# BreaV5.net
KiCad netlist of a schematic drawn in EAGLE
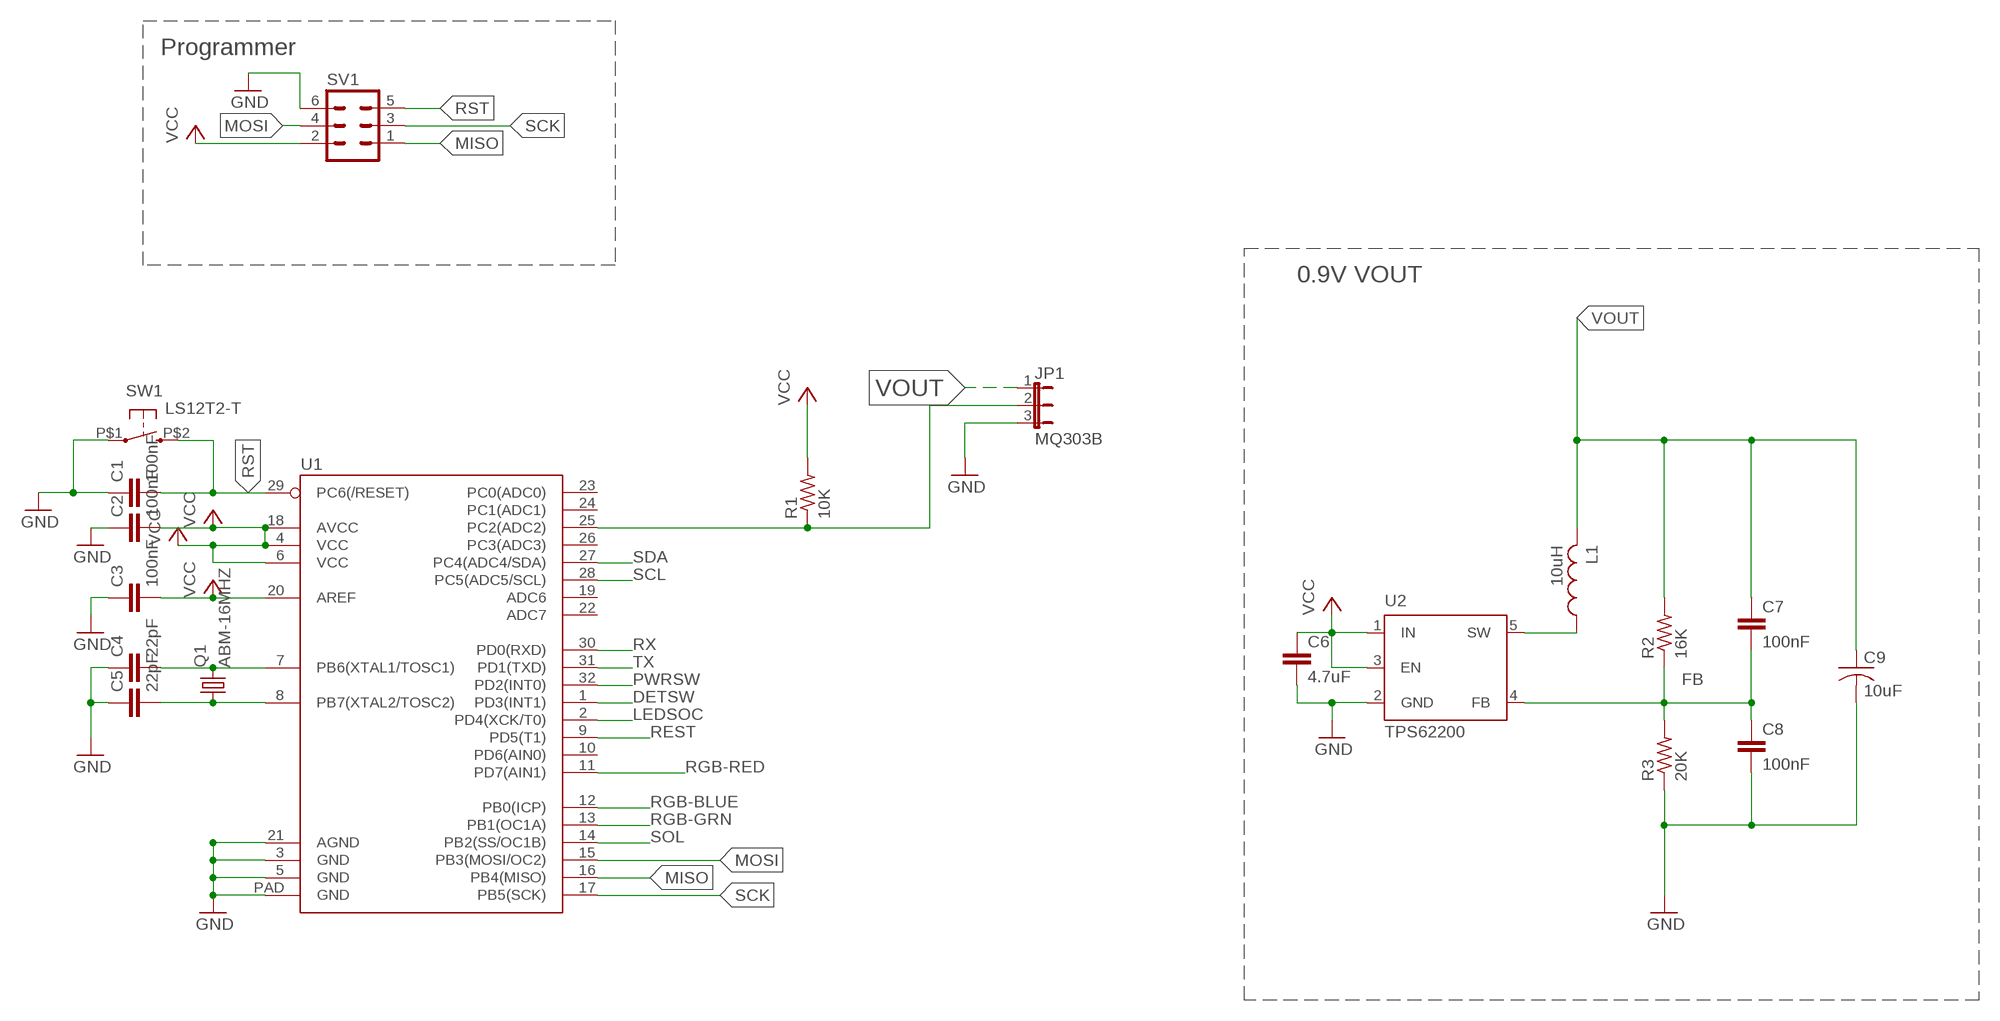
[diagram p0: schematic, sheet 1]
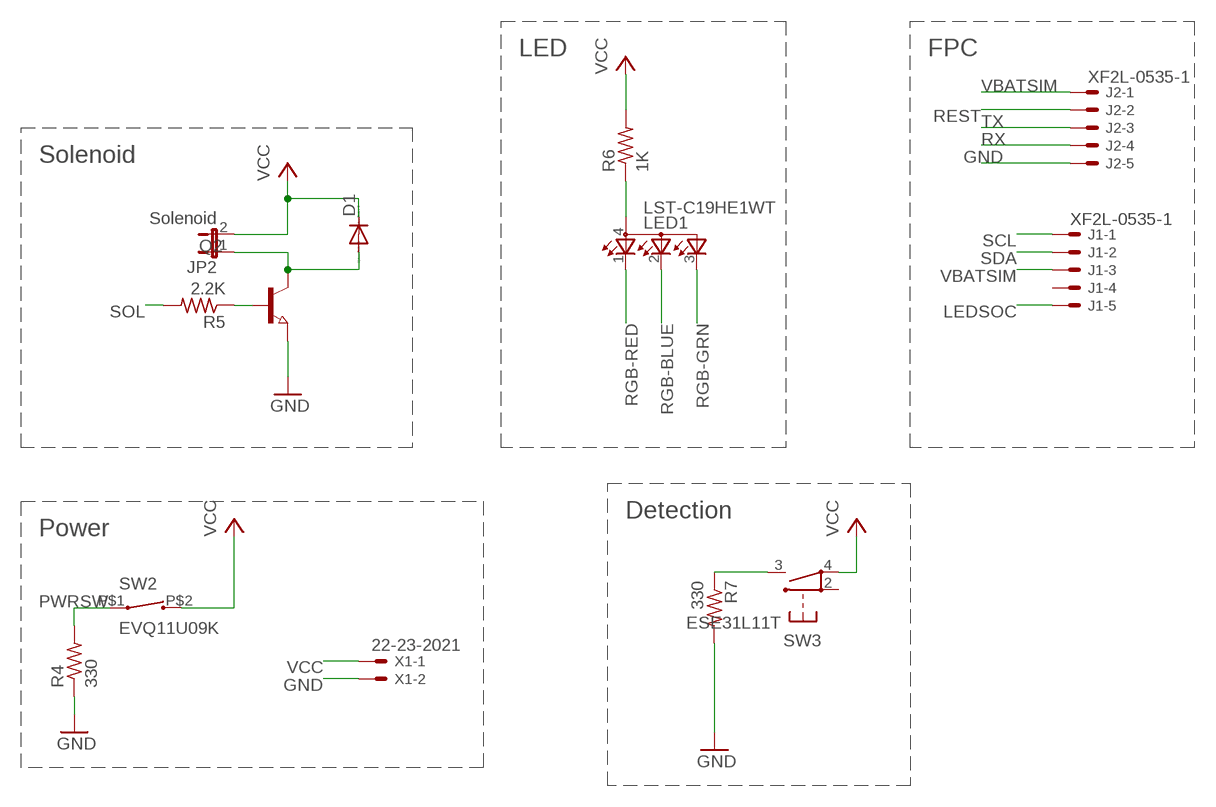
[diagram p1: schematic, sheet 2]

(export (version "E")
  (design (tool "Eeschema 10.0.6"))
  (components
    (comp (ref "C1")
      (value "100nF")
      (footprint "eagle-import:C0603")
      (libsource (lib "eagle-import") (part "C-EUC0603"))
    )
    (comp (ref "C2")
      (value "100nF")
      (footprint "eagle-import:C0603")
      (libsource (lib "eagle-import") (part "C-EUC0603"))
    )
    (comp (ref "C3")
      (value "100nF")
      (footprint "eagle-import:C0603")
      (libsource (lib "eagle-import") (part "C-EUC0603"))
    )
    (comp (ref "C4")
      (value "22pF")
      (footprint "eagle-import:C0603")
      (libsource (lib "eagle-import") (part "C-EUC0603"))
    )
    (comp (ref "C5")
      (value "22pF")
      (footprint "eagle-import:C0603")
      (libsource (lib "eagle-import") (part "C-EUC0603"))
    )
    (comp (ref "C6")
      (value "4.7uF")
      (footprint "eagle-import:C0402")
      (libsource (lib "eagle-import") (part "C-EUC0402"))
    )
    (comp (ref "C7")
      (value "100nF")
      (footprint "eagle-import:C0402")
      (libsource (lib "eagle-import") (part "C-EUC0402"))
    )
    (comp (ref "C8")
      (value "100nF")
      (footprint "eagle-import:C0402")
      (libsource (lib "eagle-import") (part "C-EUC0402"))
    )
    (comp (ref "C9")
      (value "10uF")
      (footprint "eagle-import:C0805K")
      (libsource (lib "eagle-import") (part "C-USC0805K"))
    )
    (comp (ref "JP1")
      (value "MQ303B")
      (footprint "eagle-import:JP2")
      (libsource (lib "eagle-import") (part "JP2E"))
    )
    (comp (ref "L1")
      (value "10uH")
      (footprint "eagle-import:L2825P")
      (libsource (lib "eagle-import") (part "L-USL2825P"))
    )
    (comp (ref "Q1")
      (value "ABM-16MHZ")
      (footprint "eagle-import:ABM-16MHZ")
      (libsource (lib "eagle-import") (part "ABM-16MHZ"))
    )
    (comp (ref "R1")
      (value "10K")
      (footprint "eagle-import:R0402")
      (libsource (lib "eagle-import") (part "R-US_R0402"))
    )
    (comp (ref "R2")
      (value "16K")
      (footprint "eagle-import:R0402")
      (libsource (lib "eagle-import") (part "R-US_R0402"))
    )
    (comp (ref "R3")
      (value "20K")
      (footprint "eagle-import:R0402")
      (libsource (lib "eagle-import") (part "R-US_R0402"))
    )
    (comp (ref "SV1")
      (value "MA03-2")
      (footprint "eagle-import:MA03-2")
      (libsource (lib "eagle-import") (part "MA03-2"))
    )
    (comp (ref "SW1")
      (value "LS12T2-T")
      (footprint "eagle-import:LS12T2-T")
      (libsource (lib "eagle-import") (part "LS12T2-T"))
    )
    (comp (ref "U1")
      (value "ATMEGA328P_MLFMLF32")
      (footprint "eagle-import:MLF32-PAD")
      (libsource (lib "eagle-import") (part "ATMEGA328P_MLFMLF32"))
    )
    (comp (ref "U2")
      (value "TPS62200")
      (footprint "eagle-import:TPS62200")
      (libsource (lib "eagle-import") (part "TPS62200"))
    )
    (comp (ref "D1")
      (value "DIODE-SOD123")
      (footprint "eagle-import:SOD123")
      (libsource (lib "eagle-import") (part "DIODE-SOD123"))
    )
    (comp (ref "J1")
      (value "XF2L-0535-1")
      (footprint "eagle-import:XF2L-0535-1")
      (libsource (lib "eagle-import") (part "XF2-05?35-1L"))
    )
    (comp (ref "J2")
      (value "XF2L-0535-1")
      (footprint "eagle-import:XF2L-0535-1")
      (libsource (lib "eagle-import") (part "XF2-05?35-1L"))
    )
    (comp (ref "JP2")
      (value "Solenoid")
      (footprint "eagle-import:JP1")
      (libsource (lib "eagle-import") (part "JP1E"))
    )
    (comp (ref "LED1")
      (value "LST-C19HE1WT")
      (footprint "eagle-import:LST-C19HE1WT")
      (libsource (lib "eagle-import") (part "LST-C19HE1WT"))
    )
    (comp (ref "Q2")
      (value "NPN-TRANSISTOR_SOT23")
      (footprint "eagle-import:SOT23")
      (libsource (lib "eagle-import") (part "NPN-TRANSISTOR_SOT23"))
    )
    (comp (ref "R4")
      (value "330")
      (footprint "eagle-import:R0402")
      (libsource (lib "eagle-import") (part "R-US_R0402"))
    )
    (comp (ref "R5")
      (value "2.2K")
      (footprint "eagle-import:R0402")
      (libsource (lib "eagle-import") (part "R-US_R0402"))
    )
    (comp (ref "R6")
      (value "1K")
      (footprint "eagle-import:R0402")
      (libsource (lib "eagle-import") (part "R-US_R0402"))
    )
    (comp (ref "R7")
      (value "330")
      (footprint "eagle-import:R0402")
      (libsource (lib "eagle-import") (part "R-US_R0402"))
    )
    (comp (ref "SW2")
      (value "EVQ11U09K")
      (footprint "eagle-import:EVQ11U-09K")
      (libsource (lib "eagle-import") (part "EVQ11U09K"))
    )
    (comp (ref "SW3")
      (value "ESE31L11T")
      (footprint "eagle-import:SWITCH")
      (libsource (lib "eagle-import") (part "ESE31L11T"))
    )
    (comp (ref "X1")
      (value "22-23-2021")
      (footprint "eagle-import:22-23-2021")
      (fields (field (name "MF") "MOLEX"))
      (libsource (lib "eagle-import") (part "22-23-2021"))
    )
  )
  (nets
    (net (code "1") (name "DETSW") (class "Default")
      (node (ref "R7") (pin "1") (pinfunction "1_1") (pintype "passive"))
      (node (ref "SW3") (pin "3") (pinfunction "1_3") (pintype "passive"))
      (node (ref "U1") (pin "1") (pinfunction "PD3(INT1)_1") (pintype "bidirectional"))
    )
    (net (code "2") (name "FB") (class "Default")
      (node (ref "C7") (pin "2") (pinfunction "2_2") (pintype "passive"))
      (node (ref "C8") (pin "1") (pinfunction "1_1") (pintype "passive"))
      (node (ref "R2") (pin "1") (pinfunction "1_1") (pintype "passive"))
      (node (ref "R3") (pin "2") (pinfunction "2_2") (pintype "passive"))
      (node (ref "U2") (pin "4") (pinfunction "FB_4") (pintype "passive"))
    )
    (net (code "3") (name "GND") (class "Default")
      (node (ref "C1") (pin "1") (pinfunction "1_1") (pintype "passive"))
      (node (ref "C2") (pin "1") (pinfunction "1_1") (pintype "passive"))
      (node (ref "C3") (pin "1") (pinfunction "1_1") (pintype "passive"))
      (node (ref "C4") (pin "1") (pinfunction "1_1") (pintype "passive"))
      (node (ref "C5") (pin "1") (pinfunction "1_1") (pintype "passive"))
      (node (ref "C6") (pin "2") (pinfunction "2_2") (pintype "passive"))
      (node (ref "C8") (pin "2") (pinfunction "2_2") (pintype "passive"))
      (node (ref "C9") (pin "2") (pinfunction "2_2") (pintype "passive"))
      (node (ref "J2") (pin "5") (pinfunction "MS_5") (pintype "passive"))
      (node (ref "JP1") (pin "3") (pinfunction "3_3") (pintype "passive"))
      (node (ref "Q2") (pin "2") (pinfunction "E_2") (pintype "passive"))
      (node (ref "R3") (pin "1") (pinfunction "1_1") (pintype "passive"))
      (node (ref "R4") (pin "1") (pinfunction "1_1") (pintype "passive"))
      (node (ref "R7") (pin "2") (pinfunction "2_2") (pintype "passive"))
      (node (ref "SV1") (pin "6") (pinfunction "MISO_6") (pintype "passive"))
      (node (ref "SW1") (pin "P$1") (pinfunction "S1_P$1") (pintype "passive"))
      (node (ref "U1") (pin "21") (pinfunction "AGND_21") (pintype "bidirectional"))
      (node (ref "U1") (pin "3") (pinfunction "GND_3") (pintype "bidirectional"))
      (node (ref "U1") (pin "5") (pinfunction "GND_5") (pintype "bidirectional"))
      (node (ref "U1") (pin "PAD") (pinfunction "GND_PAD") (pintype "bidirectional"))
      (node (ref "U2") (pin "2") (pinfunction "GND_2") (pintype "power_in"))
      (node (ref "X1") (pin "2") (pinfunction "S_2") (pintype "passive"))
    )
    (net (code "4") (name "LEDSOC") (class "Default")
      (node (ref "J1") (pin "5") (pinfunction "MS_5") (pintype "passive"))
      (node (ref "U1") (pin "2") (pinfunction "PD4(XCK/T0)_2") (pintype "bidirectional"))
    )
    (net (code "5") (name "MISO") (class "Default")
      (node (ref "SV1") (pin "1") (pinfunction "1_1") (pintype "passive"))
      (node (ref "U1") (pin "16") (pinfunction "PB4(MISO)_16") (pintype "bidirectional"))
    )
    (net (code "6") (name "MOSI") (class "Default")
      (node (ref "SV1") (pin "4") (pinfunction "4_4") (pintype "passive"))
      (node (ref "U1") (pin "15") (pinfunction "PB3(MOSI/OC2)_15") (pintype "bidirectional"))
    )
    (net (code "7") (name "Net-(LED1-A)") (class "Default")
      (node (ref "LED1") (pin "4") (pinfunction "A_4") (pintype "passive"))
      (node (ref "R6") (pin "1") (pinfunction "1_1") (pintype "passive"))
    )
    (net (code "8") (name "Net-(Q1-1)") (class "Default")
      (node (ref "C5") (pin "2") (pinfunction "2_2") (pintype "passive"))
      (node (ref "Q1") (pin "P$1") (pinfunction "1_P$1") (pintype "passive"))
      (node (ref "U1") (pin "8") (pinfunction "PB7(XTAL2/TOSC2)_8") (pintype "bidirectional"))
    )
    (net (code "9") (name "Net-(Q1-2)") (class "Default")
      (node (ref "C4") (pin "2") (pinfunction "2_2") (pintype "passive"))
      (node (ref "Q1") (pin "P$2") (pinfunction "2_P$2") (pintype "passive"))
      (node (ref "U1") (pin "7") (pinfunction "PB6(XTAL1/TOSC1)_7") (pintype "bidirectional"))
    )
    (net (code "10") (name "Net-(Q2-B)") (class "Default")
      (node (ref "Q2") (pin "1") (pinfunction "B_1") (pintype "passive"))
      (node (ref "R5") (pin "1") (pinfunction "1_1") (pintype "passive"))
    )
    (net (code "11") (name "Net-(Q2-C)") (class "Default")
      (node (ref "D1") (pin "A") (pinfunction "A_A") (pintype "passive"))
      (node (ref "JP2") (pin "1") (pinfunction "1_1") (pintype "passive"))
      (node (ref "Q2") (pin "3") (pinfunction "C_3") (pintype "passive"))
    )
    (net (code "12") (name "Net-(U1-PC2(ADC2))") (class "Default")
      (node (ref "JP1") (pin "2") (pinfunction "2_2") (pintype "passive"))
      (node (ref "R1") (pin "1") (pinfunction "1_1") (pintype "passive"))
      (node (ref "U1") (pin "25") (pinfunction "PC2(ADC2)_25") (pintype "bidirectional"))
    )
    (net (code "13") (name "Net-(U2-SW)") (class "Default")
      (node (ref "L1") (pin "1") (pinfunction "1_1") (pintype "passive"))
      (node (ref "U2") (pin "5") (pinfunction "SW_5") (pintype "passive"))
    )
    (net (code "14") (name "PWRSW") (class "Default")
      (node (ref "R4") (pin "2") (pinfunction "2_2") (pintype "passive"))
      (node (ref "SW2") (pin "P$1") (pinfunction "1_P$1") (pintype "passive"))
      (node (ref "U1") (pin "32") (pinfunction "PD2(INT0)_32") (pintype "bidirectional"))
    )
    (net (code "15") (name "REST") (class "Default")
      (node (ref "J2") (pin "2") (pinfunction "MS_2") (pintype "passive"))
      (node (ref "U1") (pin "9") (pinfunction "PD5(T1)_9") (pintype "bidirectional"))
    )
    (net (code "16") (name "RGB-BLUE") (class "Default")
      (node (ref "LED1") (pin "2") (pinfunction "CGREEN_2") (pintype "passive"))
      (node (ref "U1") (pin "12") (pinfunction "PB0(ICP)_12") (pintype "bidirectional"))
    )
    (net (code "17") (name "RGB-GRN") (class "Default")
      (node (ref "LED1") (pin "3") (pinfunction "CBLUE_3") (pintype "passive"))
      (node (ref "U1") (pin "13") (pinfunction "PB1(OC1A)_13") (pintype "bidirectional"))
    )
    (net (code "18") (name "RGB-RED") (class "Default")
      (node (ref "LED1") (pin "1") (pinfunction "CRED_1") (pintype "passive"))
      (node (ref "U1") (pin "11") (pinfunction "PD7(AIN1)_11") (pintype "bidirectional"))
    )
    (net (code "19") (name "RST") (class "Default")
      (node (ref "C1") (pin "2") (pinfunction "2_2") (pintype "passive"))
      (node (ref "SV1") (pin "5") (pinfunction "VTG_5") (pintype "passive"))
      (node (ref "SW1") (pin "P$2") (pinfunction "S2_P$2") (pintype "passive"))
      (node (ref "U1") (pin "29") (pinfunction "PC6(/RESET)_29") (pintype "bidirectional"))
    )
    (net (code "20") (name "RX") (class "Default")
      (node (ref "J2") (pin "4") (pinfunction "MS_4") (pintype "passive"))
      (node (ref "U1") (pin "30") (pinfunction "PD0(RXD)_30") (pintype "bidirectional"))
    )
    (net (code "21") (name "SCK") (class "Default")
      (node (ref "SV1") (pin "3") (pinfunction "3_3") (pintype "passive"))
      (node (ref "U1") (pin "17") (pinfunction "PB5(SCK)_17") (pintype "bidirectional"))
    )
    (net (code "22") (name "SCL") (class "Default")
      (node (ref "J1") (pin "1") (pinfunction "MSV_1") (pintype "passive"))
      (node (ref "U1") (pin "28") (pinfunction "PC5(ADC5/SCL)_28") (pintype "bidirectional"))
    )
    (net (code "23") (name "SDA") (class "Default")
      (node (ref "J1") (pin "2") (pinfunction "MS_2") (pintype "passive"))
      (node (ref "U1") (pin "27") (pinfunction "PC4(ADC4/SDA)_27") (pintype "bidirectional"))
    )
    (net (code "24") (name "SOL") (class "Default")
      (node (ref "R5") (pin "2") (pinfunction "2_2") (pintype "passive"))
      (node (ref "U1") (pin "14") (pinfunction "PB2(SS/OC1B)_14") (pintype "bidirectional"))
    )
    (net (code "25") (name "TX") (class "Default")
      (node (ref "J2") (pin "3") (pinfunction "MS_3") (pintype "passive"))
      (node (ref "U1") (pin "31") (pinfunction "PD1(TXD)_31") (pintype "bidirectional"))
    )
    (net (code "26") (name "VBATSIM") (class "Default")
      (node (ref "J1") (pin "3") (pinfunction "MS_3") (pintype "passive"))
      (node (ref "J2") (pin "1") (pinfunction "MSV_1") (pintype "passive"))
    )
    (net (code "27") (name "VCC") (class "Default")
      (node (ref "C2") (pin "2") (pinfunction "2_2") (pintype "passive"))
      (node (ref "C3") (pin "2") (pinfunction "2_2") (pintype "passive"))
      (node (ref "C6") (pin "1") (pinfunction "1_1") (pintype "passive"))
      (node (ref "D1") (pin "C") (pinfunction "C_C") (pintype "passive"))
      (node (ref "JP2") (pin "2") (pinfunction "2_2") (pintype "passive"))
      (node (ref "R1") (pin "2") (pinfunction "2_2") (pintype "passive"))
      (node (ref "R6") (pin "2") (pinfunction "2_2") (pintype "passive"))
      (node (ref "SV1") (pin "2") (pinfunction "2_2") (pintype "passive"))
      (node (ref "SW2") (pin "P$2") (pinfunction "2_P$2") (pintype "passive"))
      (node (ref "SW3") (pin "4") (pinfunction "C3_4") (pintype "passive"))
      (node (ref "U1") (pin "18") (pinfunction "AVCC_18") (pintype "bidirectional"))
      (node (ref "U1") (pin "20") (pinfunction "AREF_20") (pintype "bidirectional"))
      (node (ref "U1") (pin "4") (pinfunction "VCC_4") (pintype "bidirectional"))
      (node (ref "U1") (pin "6") (pinfunction "VCC_6") (pintype "bidirectional"))
      (node (ref "U2") (pin "1") (pinfunction "IN_1") (pintype "input"))
      (node (ref "U2") (pin "3") (pinfunction "EN_3") (pintype "input"))
      (node (ref "X1") (pin "1") (pinfunction "S_1") (pintype "passive"))
    )
    (net (code "28") (name "VOUT") (class "Default")
      (node (ref "C7") (pin "1") (pinfunction "1_1") (pintype "passive"))
      (node (ref "C9") (pin "1") (pinfunction "1_1") (pintype "passive"))
      (node (ref "JP1") (pin "1") (pinfunction "1_1") (pintype "passive"))
      (node (ref "L1") (pin "2") (pinfunction "2_2") (pintype "passive"))
      (node (ref "R2") (pin "2") (pinfunction "2_2") (pintype "passive"))
    )
    (net (code "29") (name "unconnected-(J1D-MS-Pad4)") (class "Default")
      (node (ref "J1") (pin "4") (pinfunction "MS_4") (pintype "passive"))
    )
    (net (code "30") (name "unconnected-(SW3-C2-Pad2)") (class "Default")
      (node (ref "SW3") (pin "2") (pinfunction "C2_2") (pintype "passive"))
    )
    (net (code "31") (name "unconnected-(U1-ADC6-Pad19)") (class "Default")
      (node (ref "U1") (pin "19") (pinfunction "ADC6_19") (pintype "bidirectional"))
    )
    (net (code "32") (name "unconnected-(U1-ADC7-Pad22)") (class "Default")
      (node (ref "U1") (pin "22") (pinfunction "ADC7_22") (pintype "bidirectional"))
    )
    (net (code "33") (name "unconnected-(U1-PC0(ADC0)-Pad23)") (class "Default")
      (node (ref "U1") (pin "23") (pinfunction "PC0(ADC0)_23") (pintype "bidirectional"))
    )
    (net (code "34") (name "unconnected-(U1-PC1(ADC1)-Pad24)") (class "Default")
      (node (ref "U1") (pin "24") (pinfunction "PC1(ADC1)_24") (pintype "bidirectional"))
    )
    (net (code "35") (name "unconnected-(U1-PC3(ADC3)-Pad26)") (class "Default")
      (node (ref "U1") (pin "26") (pinfunction "PC3(ADC3)_26") (pintype "bidirectional"))
    )
    (net (code "36") (name "unconnected-(U1-PD6(AIN0)-Pad10)") (class "Default")
      (node (ref "U1") (pin "10") (pinfunction "PD6(AIN0)_10") (pintype "bidirectional"))
    )
  )
)
